# 18F_Proto2.net
KiCad netlist of a schematic drawn in EAGLE
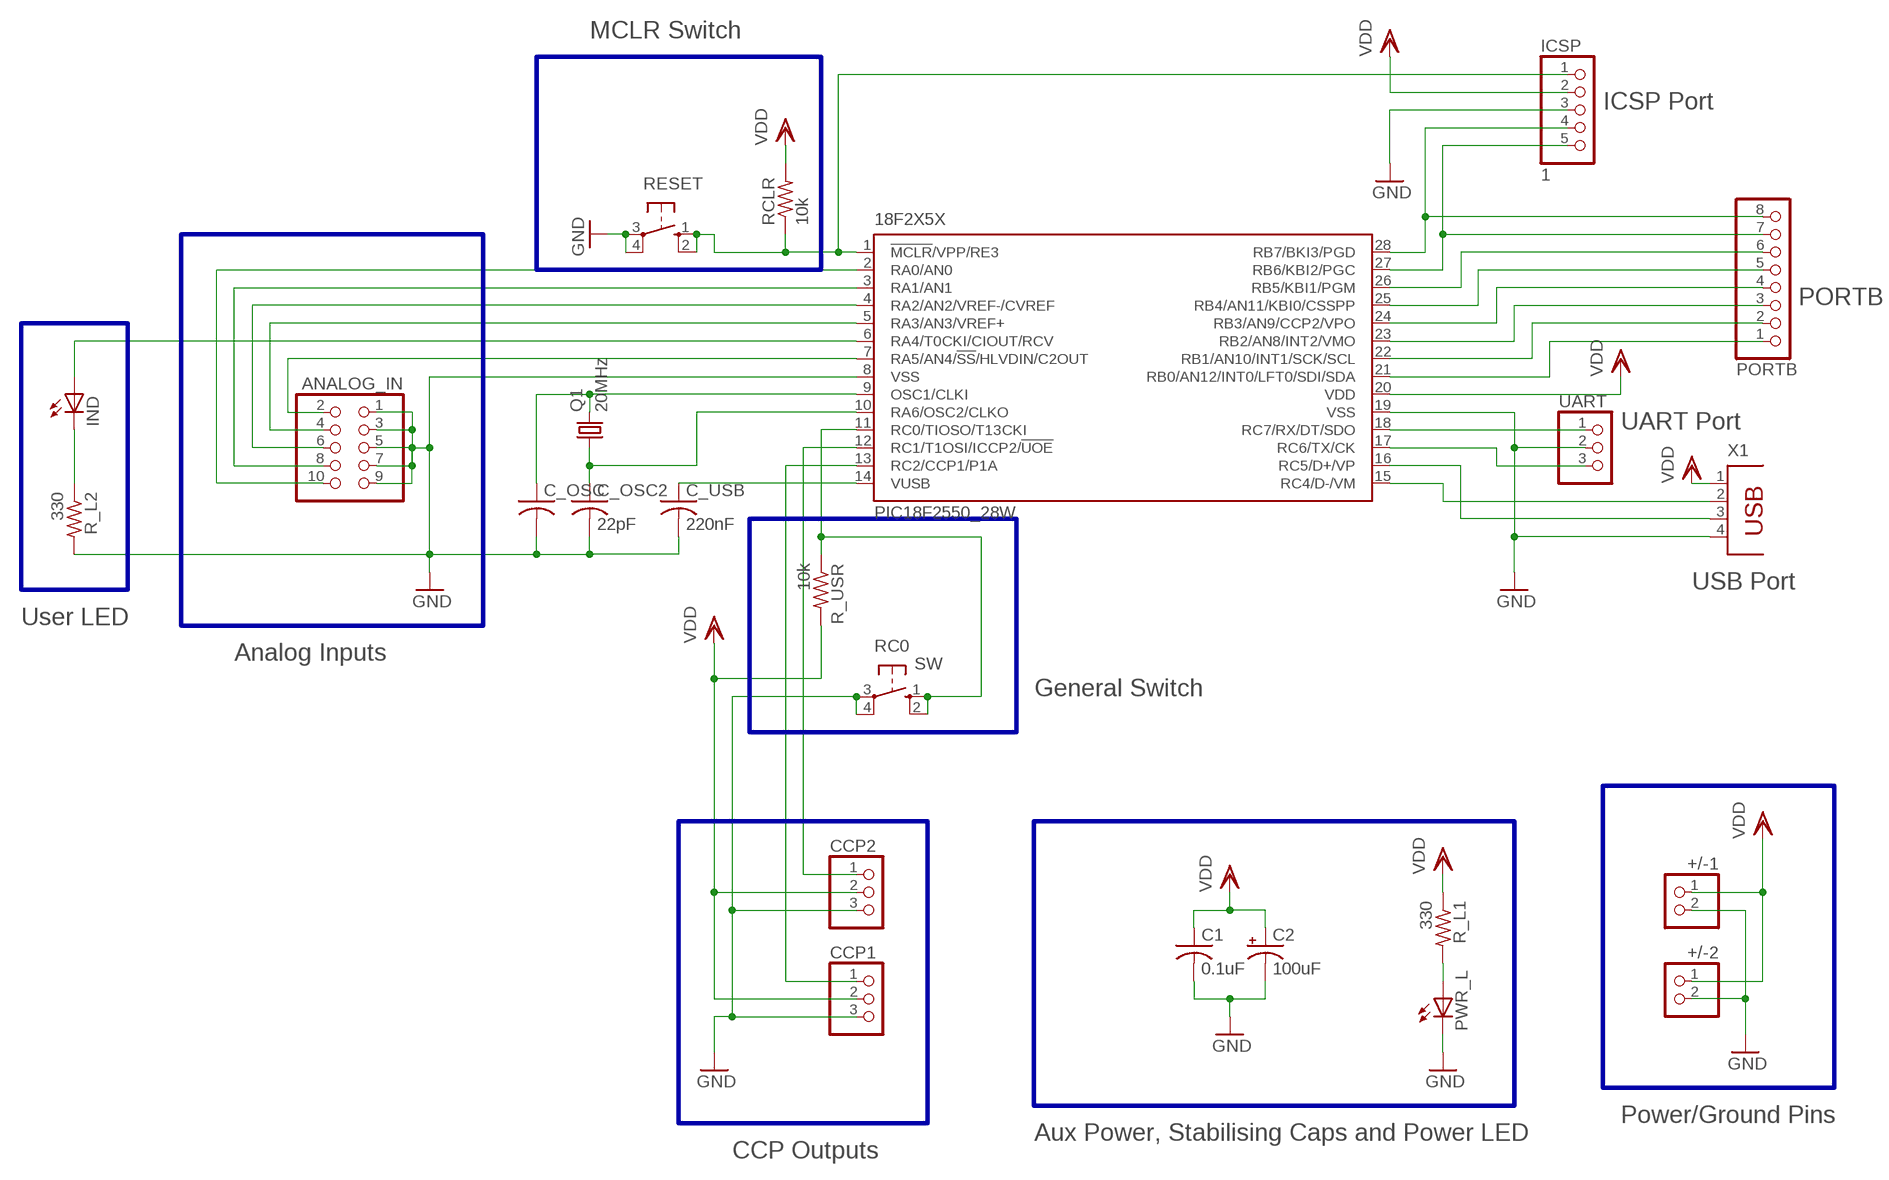
[diagram p0: schematic, sheet 1]

(export (version "E")
  (design (tool "Eeschema 10.0.6"))
  (components
    (comp (ref "+/-1")
      (value "PINHD-1X2")
      (footprint "eagle-import:1X02")
      (libsource (lib "eagle-import") (part "PINHD-1X2"))
    )
    (comp (ref "+/-2")
      (value "PINHD-1X2")
      (footprint "eagle-import:1X02")
      (libsource (lib "eagle-import") (part "PINHD-1X2"))
    )
    (comp (ref "18F2X5X")
      (value "PIC18F2550_28W")
      (footprint "eagle-import:SO28W")
      (fields (field (name "MF") "MICROCHIP") (field (name "MPN") "PIC18F2550-I/SO"))
      (libsource (lib "eagle-import") (part "PIC18F2_28W550"))
    )
    (comp (ref "ANALOG_IN")
      (value "PINHD-2X5")
      (footprint "eagle-import:2X05")
      (libsource (lib "eagle-import") (part "PINHD-2X5"))
    )
    (comp (ref "C1")
      (value "0.1uF")
      (footprint "eagle-import:C050-025X075")
      (libsource (lib "eagle-import") (part "C-US050-025X075"))
    )
    (comp (ref "C2")
      (value "100uF")
      (footprint "eagle-import:E2,5-6")
      (libsource (lib "eagle-import") (part "CPOL-USE2.5-6"))
    )
    (comp (ref "CCP1")
      (value "PINHD-1X3")
      (footprint "eagle-import:1X03")
      (libsource (lib "eagle-import") (part "PINHD-1X3"))
    )
    (comp (ref "CCP2")
      (value "PINHD-1X3")
      (footprint "eagle-import:1X03")
      (libsource (lib "eagle-import") (part "PINHD-1X3"))
    )
    (comp (ref "C_OSC")
      (value "C-US025-025X050")
      (footprint "eagle-import:C025-025X050")
      (libsource (lib "eagle-import") (part "C-US025-025X050"))
    )
    (comp (ref "C_OSC2")
      (value "22pF")
      (footprint "eagle-import:C025-025X050")
      (libsource (lib "eagle-import") (part "C-US025-025X050"))
    )
    (comp (ref "C_USB")
      (value "220nF")
      (footprint "eagle-import:C050-025X075")
      (libsource (lib "eagle-import") (part "C-US050-025X075"))
    )
    (comp (ref "ICSP")
      (value "1")
      (footprint "eagle-import:1X05")
      (libsource (lib "eagle-import") (part "PINHD-1X5"))
    )
    (comp (ref "IND")
      (value "LED3MM")
      (footprint "eagle-import:LED3MM")
      (libsource (lib "eagle-import") (part "LED3MM"))
    )
    (comp (ref "PORTB")
      (value "PINHD-1X8")
      (footprint "eagle-import:1X08")
      (libsource (lib "eagle-import") (part "PINHD-1X8"))
    )
    (comp (ref "PWR_L")
      (value "LED3MM")
      (footprint "eagle-import:LED3MM")
      (libsource (lib "eagle-import") (part "LED3MM"))
    )
    (comp (ref "Q1")
      (value "20MHz")
      (footprint "eagle-import:HC49_S")
      (libsource (lib "eagle-import") (part "CRYSTALHC49S"))
    )
    (comp (ref "RC0")
      (value "SW")
      (footprint "eagle-import:B3F-10XX")
      (fields (field (name "MPN") "B3F-1000"))
      (libsource (lib "eagle-import") (part "10-XX"))
    )
    (comp (ref "RCLR")
      (value "10k")
      (footprint "eagle-import:0204_7")
      (libsource (lib "eagle-import") (part "R-US_0204/7"))
    )
    (comp (ref "RESET")
      (value "10-XX")
      (footprint "eagle-import:B3F-10XX")
      (fields (field (name "MPN") "B3F-1000"))
      (libsource (lib "eagle-import") (part "10-XX"))
    )
    (comp (ref "R_L1")
      (value "330")
      (footprint "eagle-import:0204_7")
      (libsource (lib "eagle-import") (part "R-US_0204/7"))
    )
    (comp (ref "R_L2")
      (value "330")
      (footprint "eagle-import:0207_10")
      (libsource (lib "eagle-import") (part "R-US_0207/10"))
    )
    (comp (ref "R_USR")
      (value "10k")
      (footprint "eagle-import:0204_7")
      (libsource (lib "eagle-import") (part "R-US_0204/7"))
    )
    (comp (ref "UART")
      (value "PINHD-1X3")
      (footprint "eagle-import:1X03")
      (libsource (lib "eagle-import") (part "PINHD-1X3"))
    )
    (comp (ref "X1")
      (value "PN61729")
      (footprint "eagle-import:PN61729")
      (libsource (lib "eagle-import") (part "PN61729"))
    )
  )
  (nets
    (net (code "1") (name "GND") (class "Default")
      (node (ref "+/-1") (pin "2") (pinfunction "2_2") (pintype "passive"))
      (node (ref "+/-2") (pin "2") (pinfunction "2_2") (pintype "passive"))
      (node (ref "18F2X5X") (pin "19") (pinfunction "VSS_19") (pintype "power_in"))
      (node (ref "18F2X5X") (pin "8") (pinfunction "VSS_8") (pintype "power_in"))
      (node (ref "ANALOG_IN") (pin "1") (pinfunction "1_1") (pintype "passive"))
      (node (ref "ANALOG_IN") (pin "3") (pinfunction "3_3") (pintype "passive"))
      (node (ref "ANALOG_IN") (pin "5") (pinfunction "5_5") (pintype "passive"))
      (node (ref "ANALOG_IN") (pin "7") (pinfunction "7_7") (pintype "passive"))
      (node (ref "ANALOG_IN") (pin "9") (pinfunction "9_9") (pintype "passive"))
      (node (ref "C1") (pin "2") (pinfunction "2_2") (pintype "passive"))
      (node (ref "C2") (pin "-") (pinfunction "-_-") (pintype "passive"))
      (node (ref "CCP1") (pin "3") (pinfunction "3_3") (pintype "passive"))
      (node (ref "CCP2") (pin "3") (pinfunction "3_3") (pintype "passive"))
      (node (ref "C_OSC") (pin "2") (pinfunction "2_2") (pintype "passive"))
      (node (ref "C_OSC2") (pin "2") (pinfunction "2_2") (pintype "passive"))
      (node (ref "C_USB") (pin "2") (pinfunction "2_2") (pintype "passive"))
      (node (ref "ICSP") (pin "3") (pinfunction "3_3") (pintype "passive"))
      (node (ref "PWR_L") (pin "K") (pinfunction "C_K") (pintype "passive"))
      (node (ref "RC0") (pin "3") (pinfunction "P_3") (pintype "passive"))
      (node (ref "RC0") (pin "4") (pinfunction "P1_4") (pintype "passive"))
      (node (ref "RESET") (pin "3") (pinfunction "P_3") (pintype "passive"))
      (node (ref "RESET") (pin "4") (pinfunction "P1_4") (pintype "passive"))
      (node (ref "R_L2") (pin "2") (pinfunction "2_2") (pintype "passive"))
      (node (ref "UART") (pin "2") (pinfunction "2_2") (pintype "passive"))
      (node (ref "X1") (pin "4") (pinfunction "4_4") (pintype "passive"))
    )
    (net (code "2") (name "Net-(18F2X5X-OSC1{slash}CLKI)") (class "Default")
      (node (ref "18F2X5X") (pin "9") (pinfunction "OSC1/CLKI_9") (pintype "input"))
      (node (ref "C_OSC") (pin "1") (pinfunction "1_1") (pintype "passive"))
      (node (ref "Q1") (pin "2") (pinfunction "2_2") (pintype "passive"))
    )
    (net (code "3") (name "Net-(18F2X5X-RA0{slash}AN0)") (class "Default")
      (node (ref "18F2X5X") (pin "2") (pinfunction "RA0/AN0_2") (pintype "bidirectional"))
      (node (ref "ANALOG_IN") (pin "10") (pinfunction "10_10") (pintype "passive"))
    )
    (net (code "4") (name "Net-(18F2X5X-RA1{slash}AN1)") (class "Default")
      (node (ref "18F2X5X") (pin "3") (pinfunction "RA1/AN1_3") (pintype "bidirectional"))
      (node (ref "ANALOG_IN") (pin "8") (pinfunction "8_8") (pintype "passive"))
    )
    (net (code "5") (name "Net-(18F2X5X-RA2{slash}AN2{slash}VREF-{slash}CVREF)") (class "Default")
      (node (ref "18F2X5X") (pin "4") (pinfunction "RA2/AN2/VREF-/CVREF_4") (pintype "bidirectional"))
      (node (ref "ANALOG_IN") (pin "6") (pinfunction "6_6") (pintype "passive"))
    )
    (net (code "6") (name "Net-(18F2X5X-RA3{slash}AN3{slash}VREF+)") (class "Default")
      (node (ref "18F2X5X") (pin "5") (pinfunction "RA3/AN3/VREF+_5") (pintype "bidirectional"))
      (node (ref "ANALOG_IN") (pin "4") (pinfunction "4_4") (pintype "passive"))
    )
    (net (code "7") (name "Net-(18F2X5X-RA4{slash}T0CKI{slash}CIOUT{slash}RCV)") (class "Default")
      (node (ref "18F2X5X") (pin "6") (pinfunction "RA4/T0CKI/CIOUT/RCV_6") (pintype "bidirectional"))
      (node (ref "IND") (pin "A") (pinfunction "A_A") (pintype "passive"))
    )
    (net (code "8") (name "Net-(18F2X5X-RA5{slash}AN4{slash}~{SS}{slash}HLVDIN{slash}C2OUT)") (class "Default")
      (node (ref "18F2X5X") (pin "7") (pinfunction "RA5/AN4/~{SS}/HLVDIN/C2OUT_7") (pintype "bidirectional"))
      (node (ref "ANALOG_IN") (pin "2") (pinfunction "2_2") (pintype "passive"))
    )
    (net (code "9") (name "Net-(18F2X5X-RA6{slash}OSC2{slash}CLKO)") (class "Default")
      (node (ref "18F2X5X") (pin "10") (pinfunction "RA6/OSC2/CLKO_10") (pintype "output"))
      (node (ref "C_OSC2") (pin "1") (pinfunction "1_1") (pintype "passive"))
      (node (ref "Q1") (pin "1") (pinfunction "1_1") (pintype "passive"))
    )
    (net (code "10") (name "Net-(18F2X5X-RB0{slash}AN12{slash}INT0{slash}LFT0{slash}SDI{slash}SDA)") (class "Default")
      (node (ref "18F2X5X") (pin "21") (pinfunction "RB0/AN12/INT0/LFT0/SDI/SDA_21") (pintype "bidirectional"))
      (node (ref "PORTB") (pin "1") (pinfunction "1_1") (pintype "passive"))
    )
    (net (code "11") (name "Net-(18F2X5X-RB1{slash}AN10{slash}INT1{slash}SCK{slash}SCL)") (class "Default")
      (node (ref "18F2X5X") (pin "22") (pinfunction "RB1/AN10/INT1/SCK/SCL_22") (pintype "bidirectional"))
      (node (ref "PORTB") (pin "2") (pinfunction "2_2") (pintype "passive"))
    )
    (net (code "12") (name "Net-(18F2X5X-RB2{slash}AN8{slash}INT2{slash}VMO)") (class "Default")
      (node (ref "18F2X5X") (pin "23") (pinfunction "RB2/AN8/INT2/VMO_23") (pintype "bidirectional"))
      (node (ref "PORTB") (pin "3") (pinfunction "3_3") (pintype "passive"))
    )
    (net (code "13") (name "Net-(18F2X5X-RB3{slash}AN9{slash}CCP2{slash}VPO)") (class "Default")
      (node (ref "18F2X5X") (pin "24") (pinfunction "RB3/AN9/CCP2/VPO_24") (pintype "bidirectional"))
      (node (ref "PORTB") (pin "4") (pinfunction "4_4") (pintype "passive"))
    )
    (net (code "14") (name "Net-(18F2X5X-RB4{slash}AN11{slash}KBI0{slash}CSSPP)") (class "Default")
      (node (ref "18F2X5X") (pin "25") (pinfunction "RB4/AN11/KBI0/CSSPP_25") (pintype "bidirectional"))
      (node (ref "PORTB") (pin "5") (pinfunction "5_5") (pintype "passive"))
    )
    (net (code "15") (name "Net-(18F2X5X-RB5{slash}KBI1{slash}PGM)") (class "Default")
      (node (ref "18F2X5X") (pin "26") (pinfunction "RB5/KBI1/PGM_26") (pintype "bidirectional"))
      (node (ref "PORTB") (pin "6") (pinfunction "6_6") (pintype "passive"))
    )
    (net (code "16") (name "Net-(18F2X5X-RB6{slash}KBI2{slash}PGC)") (class "Default")
      (node (ref "18F2X5X") (pin "27") (pinfunction "RB6/KBI2/PGC_27") (pintype "bidirectional"))
      (node (ref "ICSP") (pin "5") (pinfunction "5_5") (pintype "passive"))
      (node (ref "PORTB") (pin "7") (pinfunction "7_7") (pintype "passive"))
    )
    (net (code "17") (name "Net-(18F2X5X-RB7{slash}BKI3{slash}PGD)") (class "Default")
      (node (ref "18F2X5X") (pin "28") (pinfunction "RB7/BKI3/PGD_28") (pintype "bidirectional"))
      (node (ref "ICSP") (pin "4") (pinfunction "4_4") (pintype "passive"))
      (node (ref "PORTB") (pin "8") (pinfunction "8_8") (pintype "passive"))
    )
    (net (code "18") (name "Net-(18F2X5X-RC0{slash}TIOSO{slash}T13CKI)") (class "Default")
      (node (ref "18F2X5X") (pin "11") (pinfunction "RC0/TIOSO/T13CKI_11") (pintype "bidirectional"))
      (node (ref "RC0") (pin "1") (pinfunction "S_1") (pintype "passive"))
      (node (ref "RC0") (pin "2") (pinfunction "S1_2") (pintype "passive"))
      (node (ref "R_USR") (pin "1") (pinfunction "1_1") (pintype "passive"))
    )
    (net (code "19") (name "Net-(18F2X5X-RC1{slash}T1OSI{slash}ICCP2{slash}~{UOE})") (class "Default")
      (node (ref "18F2X5X") (pin "12") (pinfunction "RC1/T1OSI/ICCP2/~{UOE}_12") (pintype "bidirectional"))
      (node (ref "CCP2") (pin "1") (pinfunction "1_1") (pintype "passive"))
    )
    (net (code "20") (name "Net-(18F2X5X-RC2{slash}CCP1{slash}P1A)") (class "Default")
      (node (ref "18F2X5X") (pin "13") (pinfunction "RC2/CCP1/P1A_13") (pintype "bidirectional"))
      (node (ref "CCP1") (pin "1") (pinfunction "1_1") (pintype "passive"))
    )
    (net (code "21") (name "Net-(18F2X5X-RC4{slash}D-{slash}VM)") (class "Default")
      (node (ref "18F2X5X") (pin "15") (pinfunction "RC4/D-/VM_15") (pintype "bidirectional"))
      (node (ref "X1") (pin "2") (pinfunction "2_2") (pintype "passive"))
    )
    (net (code "22") (name "Net-(18F2X5X-RC5{slash}D+{slash}VP)") (class "Default")
      (node (ref "18F2X5X") (pin "16") (pinfunction "RC5/D+/VP_16") (pintype "bidirectional"))
      (node (ref "X1") (pin "3") (pinfunction "3_3") (pintype "passive"))
    )
    (net (code "23") (name "Net-(18F2X5X-RC6{slash}TX{slash}CK)") (class "Default")
      (node (ref "18F2X5X") (pin "17") (pinfunction "RC6/TX/CK_17") (pintype "bidirectional"))
      (node (ref "UART") (pin "3") (pinfunction "3_3") (pintype "passive"))
    )
    (net (code "24") (name "Net-(18F2X5X-RC7{slash}RX{slash}DT{slash}SDO)") (class "Default")
      (node (ref "18F2X5X") (pin "18") (pinfunction "RC7/RX/DT/SDO_18") (pintype "bidirectional"))
      (node (ref "UART") (pin "1") (pinfunction "1_1") (pintype "passive"))
    )
    (net (code "25") (name "Net-(18F2X5X-VUSB)") (class "Default")
      (node (ref "18F2X5X") (pin "14") (pinfunction "VUSB_14") (pintype "bidirectional"))
      (node (ref "C_USB") (pin "1") (pinfunction "1_1") (pintype "passive"))
    )
    (net (code "26") (name "Net-(18F2X5X-~{MCLR}{slash}VPP{slash}RE3)") (class "Default")
      (node (ref "18F2X5X") (pin "1") (pinfunction "~{MCLR}/VPP/RE3_1") (pintype "input"))
      (node (ref "ICSP") (pin "1") (pinfunction "1_1") (pintype "passive"))
      (node (ref "RCLR") (pin "1") (pinfunction "1_1") (pintype "passive"))
      (node (ref "RESET") (pin "1") (pinfunction "S_1") (pintype "passive"))
      (node (ref "RESET") (pin "2") (pinfunction "S1_2") (pintype "passive"))
    )
    (net (code "27") (name "Net-(IND-C)") (class "Default")
      (node (ref "IND") (pin "K") (pinfunction "C_K") (pintype "passive"))
      (node (ref "R_L2") (pin "1") (pinfunction "1_1") (pintype "passive"))
    )
    (net (code "28") (name "Net-(PWR_L-PadA)") (class "Default")
      (node (ref "PWR_L") (pin "A") (pinfunction "A_A") (pintype "passive"))
      (node (ref "R_L1") (pin "2") (pinfunction "2_2") (pintype "passive"))
    )
    (net (code "29") (name "VDD") (class "Default")
      (node (ref "+/-1") (pin "1") (pinfunction "1_1") (pintype "passive"))
      (node (ref "+/-2") (pin "1") (pinfunction "1_1") (pintype "passive"))
      (node (ref "18F2X5X") (pin "20") (pinfunction "VDD_20") (pintype "power_in"))
      (node (ref "C1") (pin "1") (pinfunction "1_1") (pintype "passive"))
      (node (ref "C2") (pin "+") (pinfunction "+_+") (pintype "passive"))
      (node (ref "CCP1") (pin "2") (pinfunction "2_2") (pintype "passive"))
      (node (ref "CCP2") (pin "2") (pinfunction "2_2") (pintype "passive"))
      (node (ref "ICSP") (pin "2") (pinfunction "2_2") (pintype "passive"))
      (node (ref "RCLR") (pin "2") (pinfunction "2_2") (pintype "passive"))
      (node (ref "R_L1") (pin "1") (pinfunction "1_1") (pintype "passive"))
      (node (ref "R_USR") (pin "2") (pinfunction "2_2") (pintype "passive"))
      (node (ref "X1") (pin "1") (pinfunction "1_1") (pintype "passive"))
    )
  )
)
